# STM32F446xx_Schematic_design.net
KiCad netlist of a schematic drawn in Altium Designer
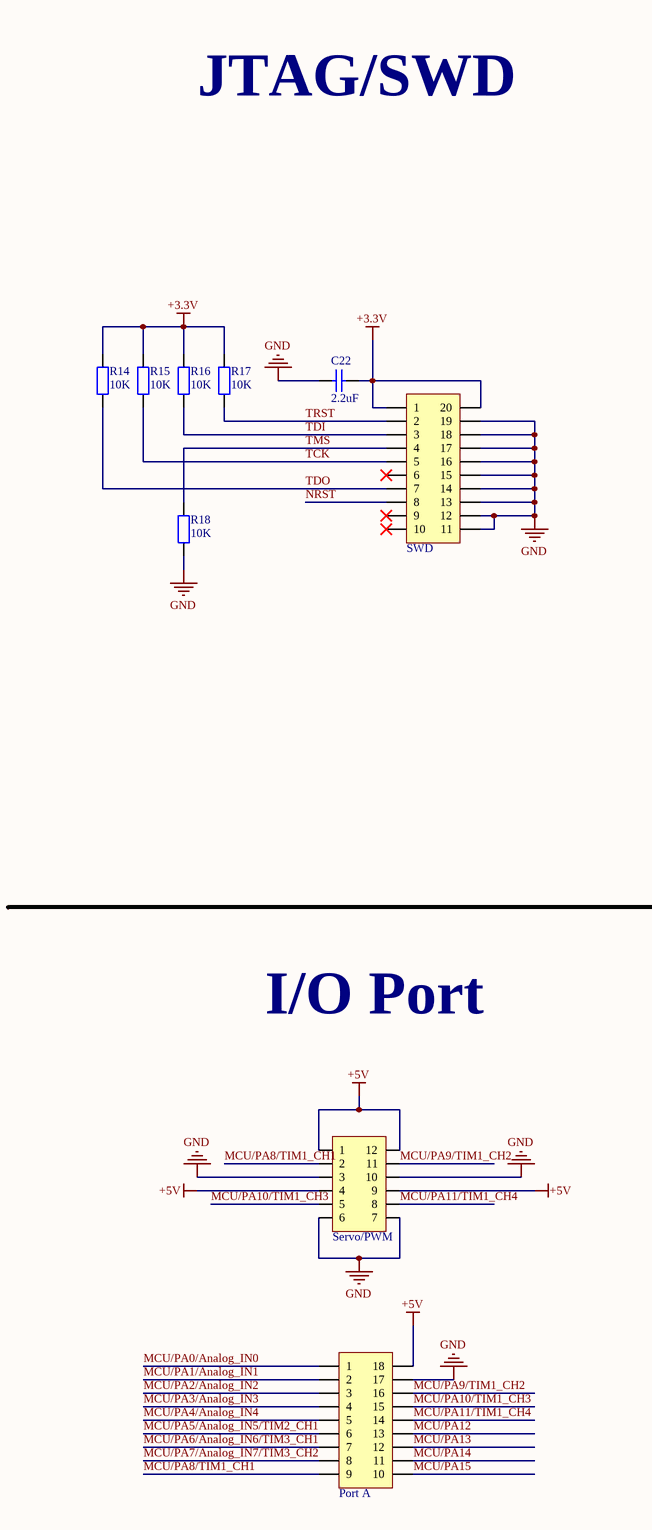
[diagram p0: STM32F446xx Schematic design.SchDoc, top left]
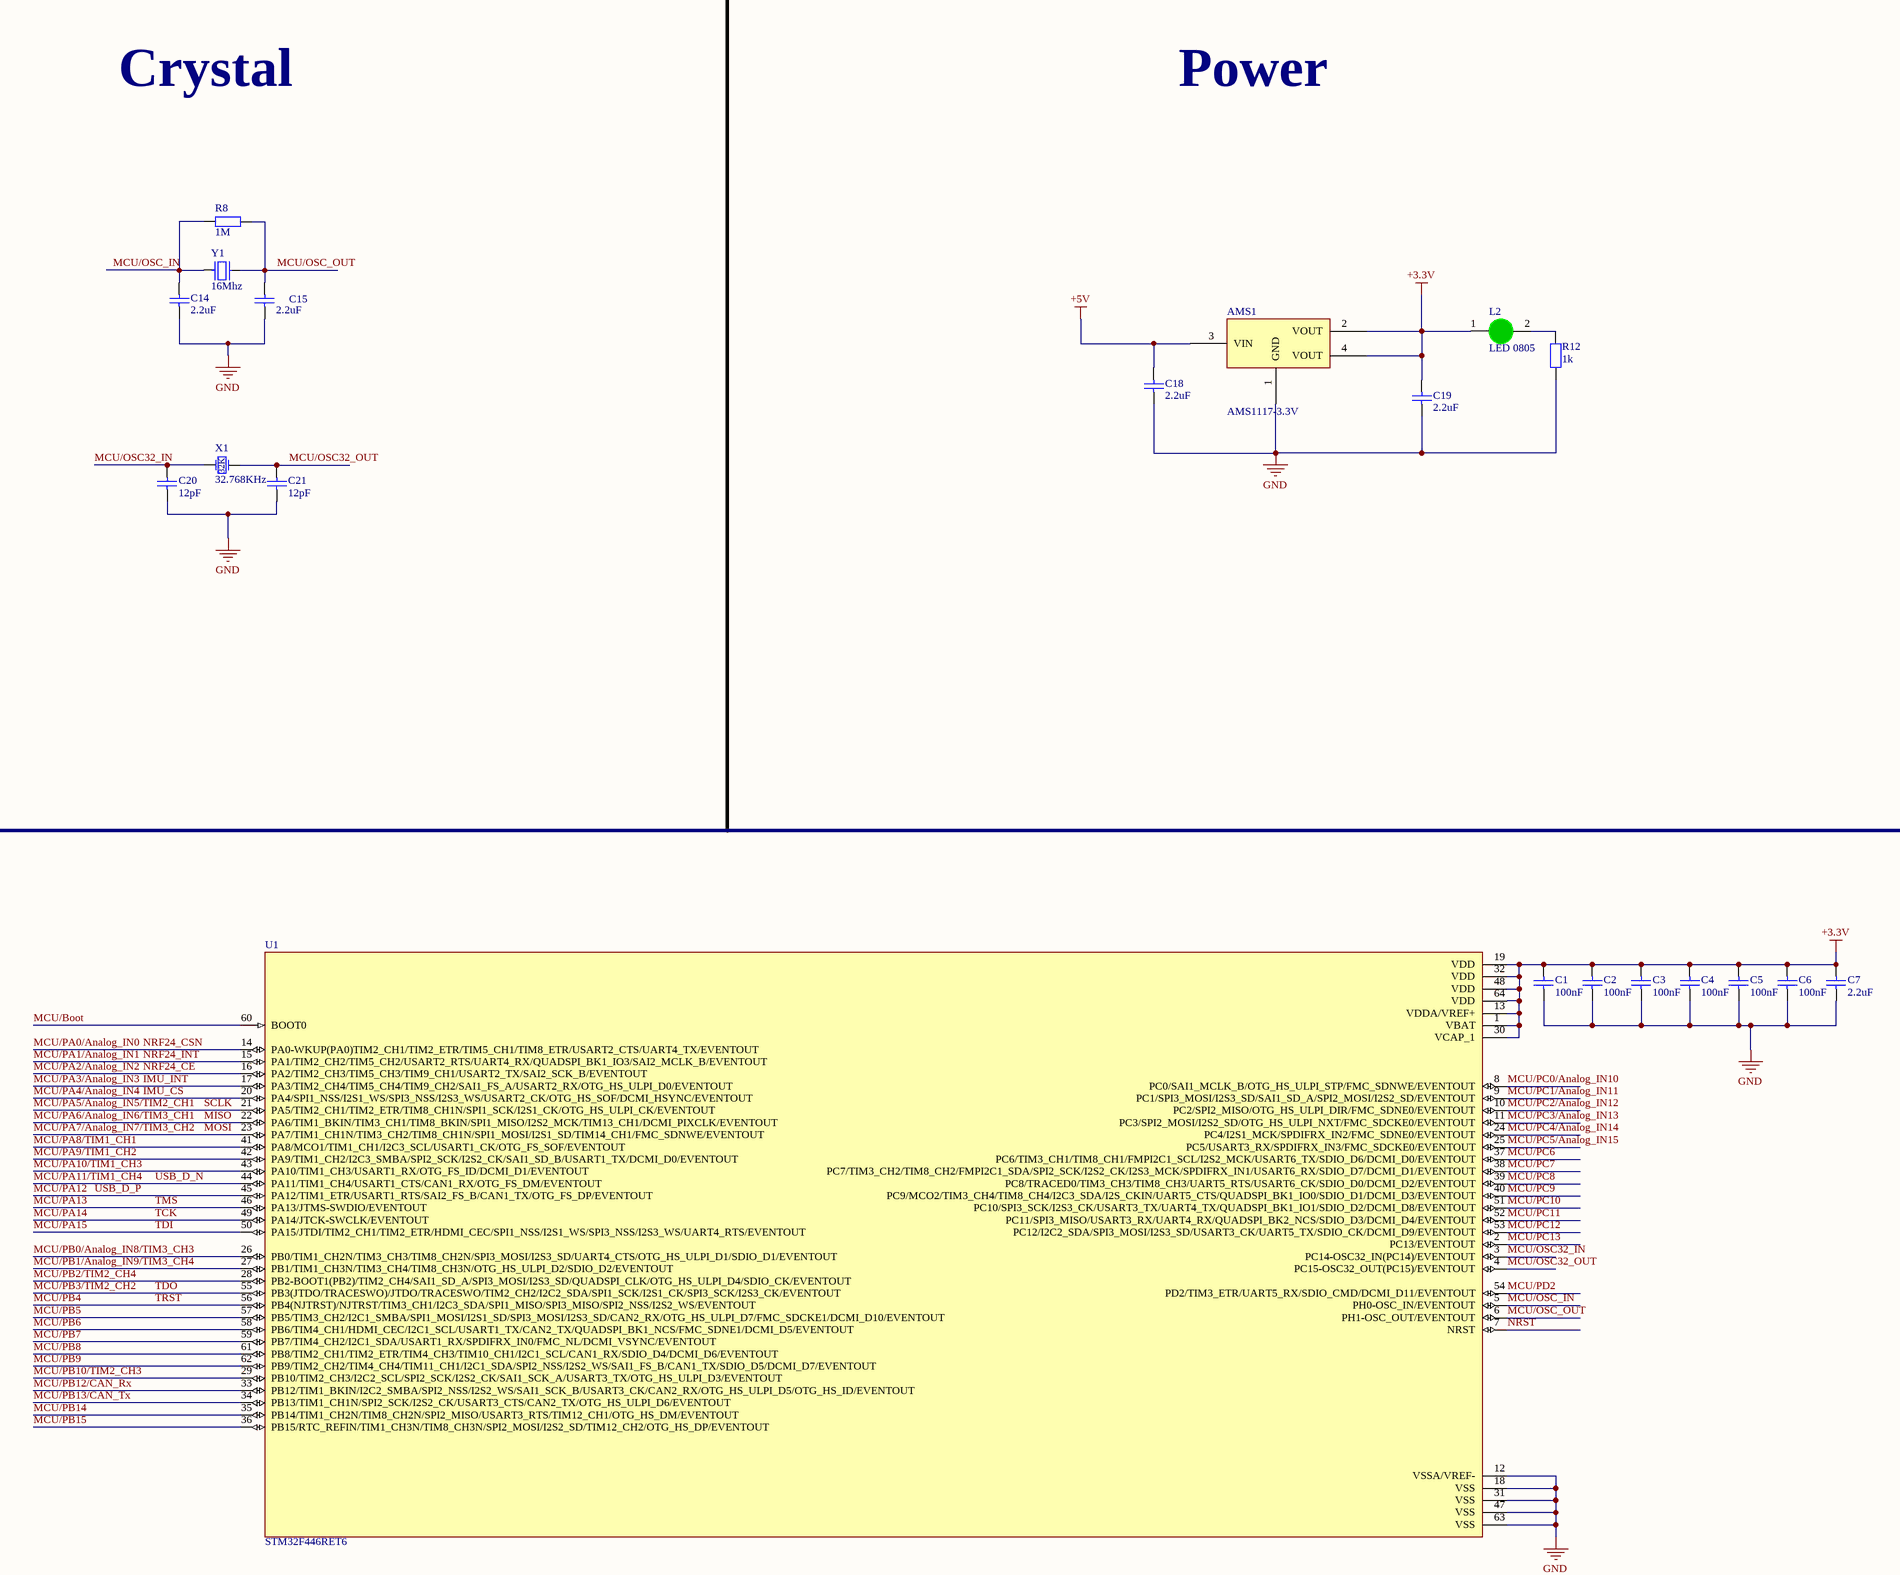
[diagram p1: STM32F446xx Schematic design.SchDoc, top middle]
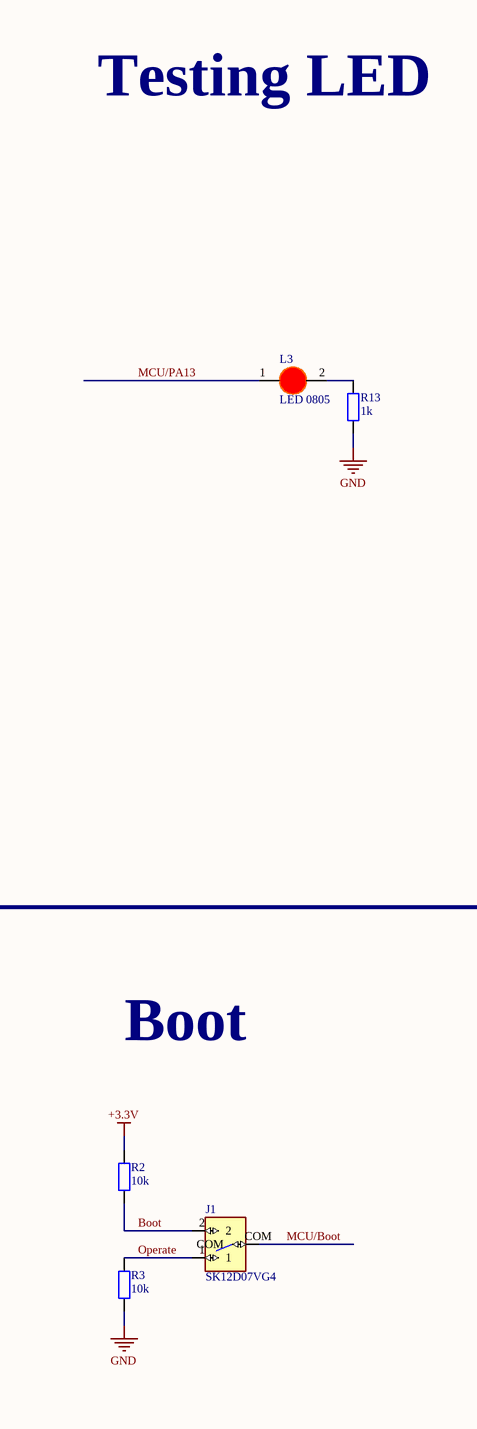
[diagram p2: STM32F446xx Schematic design.SchDoc, top right]
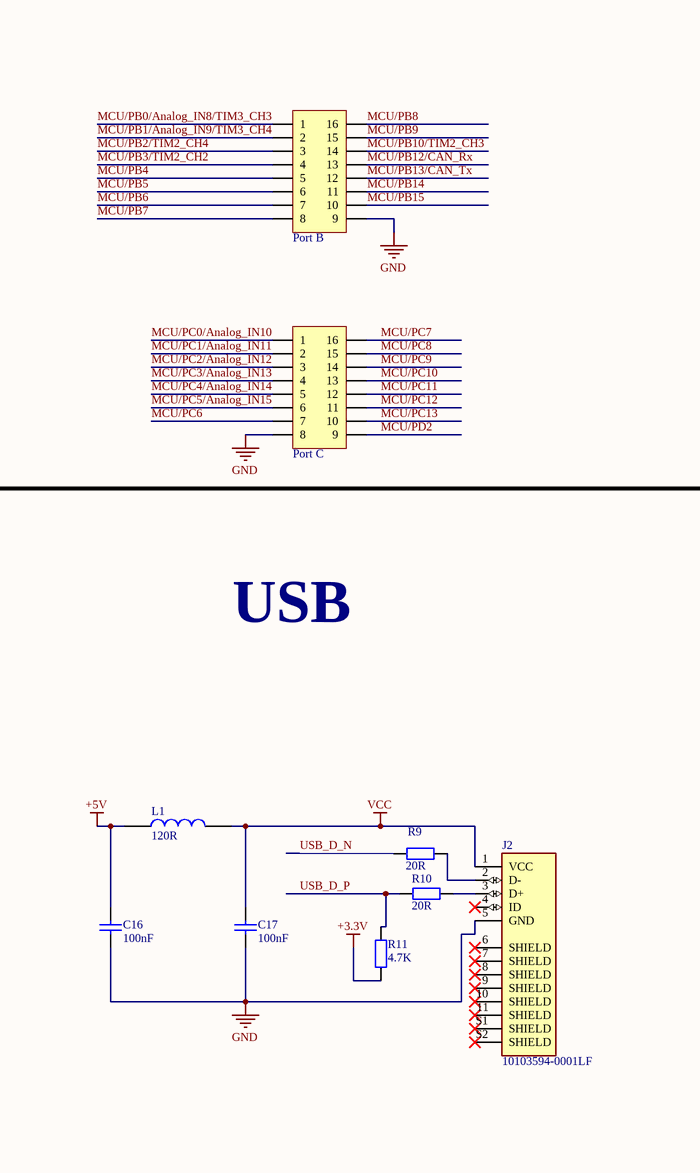
[diagram p3: STM32F446xx Schematic design.SchDoc, bottom left]
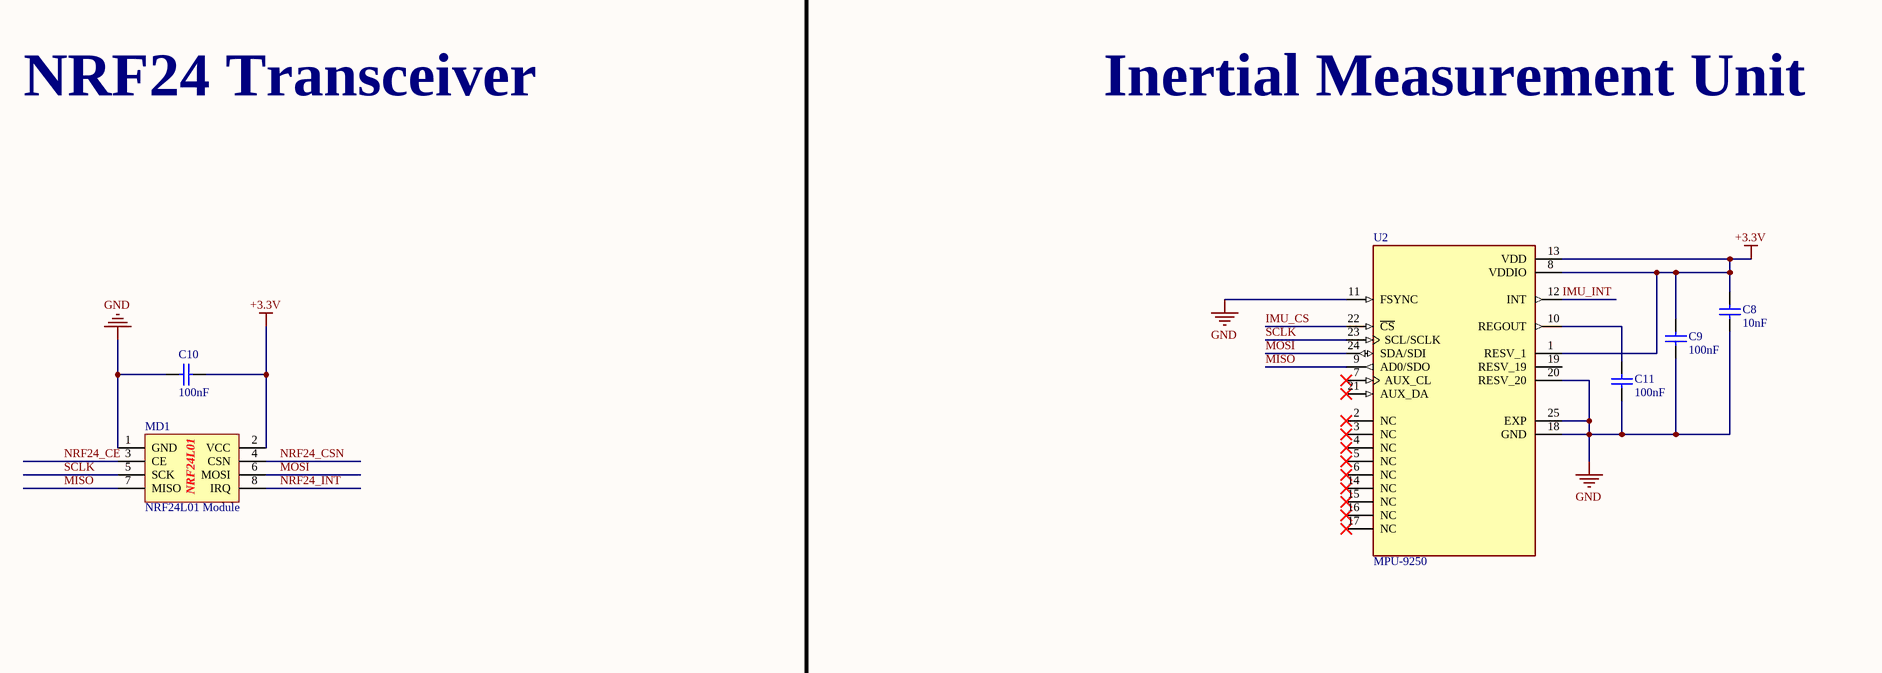
[diagram p4: STM32F446xx Schematic design.SchDoc, bottom middle]
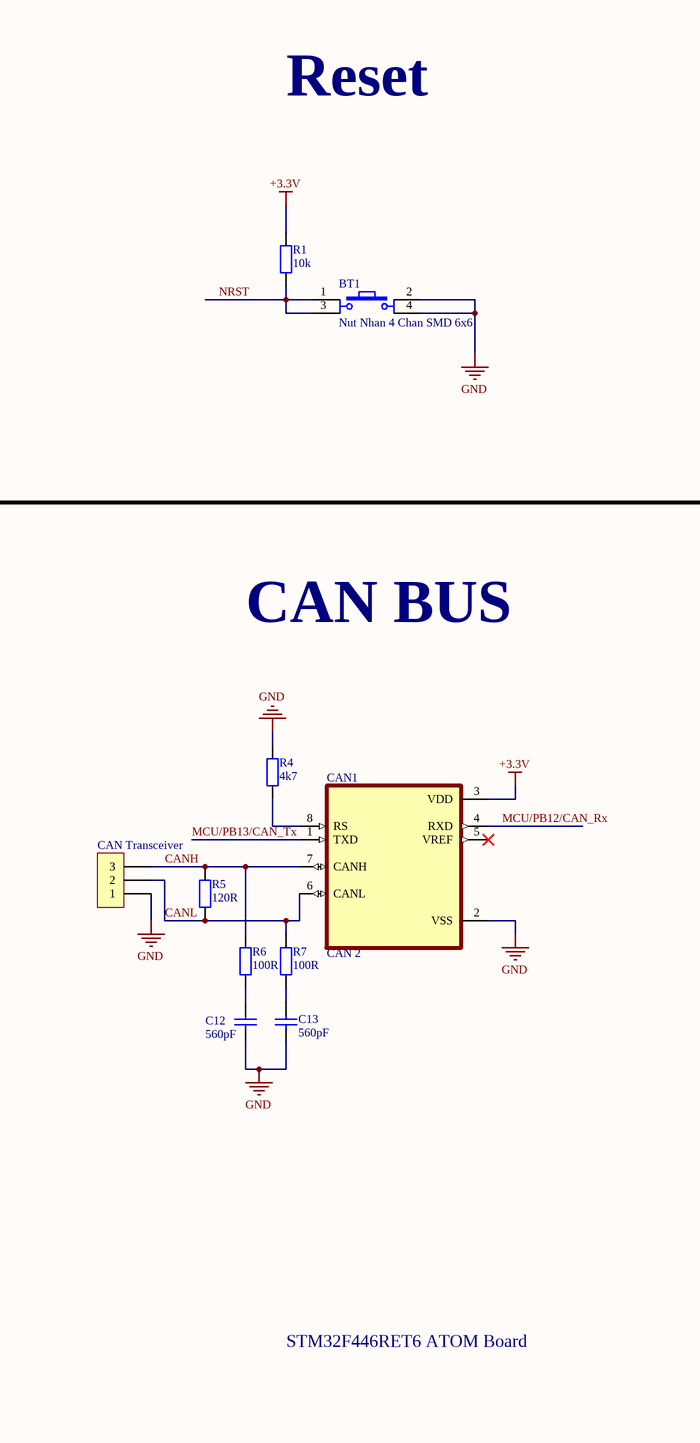
[diagram p5: STM32F446xx Schematic design.SchDoc, bottom right]

(export (version "E")
  (design (tool "Eeschema 10.0.6"))
  (components
    (comp (ref "AMS1")
      (value "AMS1117-3.3V")
      (footprint "SOT223")
      (description "Dán")
      (libsource (lib "Altium_Lib_by_KhueNguyenCreator") (part "AMS1117 SMD"))
    )
    (comp (ref "BT1")
      (value "Nut Nhan 4 Chan SMD 6x6")
      (footprint "Nut Nhan 4 Chan SMD 6x6")
      (description "Nut Nhan 4 Chan 6.2x6.2x3.5")
      (libsource (lib "Altium_Lib_by_KhueNguyenCreator") (part "Nut Nhan 4 Chan SMD 6x6"))
    )
    (comp (ref "C1")
      (value "100nF")
      (footprint "tu 0805")
      (description "Dán")
      (libsource (lib "Altium_Lib_by_KhueNguyenCreator") (part "Tu 0805 10pF 50V 10%"))
    )
    (comp (ref "C2")
      (value "100nF")
      (footprint "tu 0805")
      (description "Dán")
      (libsource (lib "Altium_Lib_by_KhueNguyenCreator") (part "Tu 0805 10pF 50V 10%"))
    )
    (comp (ref "C3")
      (value "100nF")
      (footprint "tu 0805")
      (description "Dán")
      (libsource (lib "Altium_Lib_by_KhueNguyenCreator") (part "Tu 0805 10pF 50V 10%"))
    )
    (comp (ref "C4")
      (value "100nF")
      (footprint "tu 0805")
      (description "Dán")
      (libsource (lib "Altium_Lib_by_KhueNguyenCreator") (part "Tu 0805 10pF 50V 10%"))
    )
    (comp (ref "C5")
      (value "100nF")
      (footprint "tu 0805")
      (description "Dán")
      (libsource (lib "Altium_Lib_by_KhueNguyenCreator") (part "Tu 0805 10pF 50V 10%"))
    )
    (comp (ref "C6")
      (value "100nF")
      (footprint "tu 0805")
      (description "Dán")
      (libsource (lib "Altium_Lib_by_KhueNguyenCreator") (part "Tu 0805 10pF 50V 10%"))
    )
    (comp (ref "C7")
      (value "2.2uF")
      (footprint "tu 0805")
      (description "Dán")
      (libsource (lib "Altium_Lib_by_KhueNguyenCreator") (part "Tu 0805 10pF 50V 10%"))
    )
    (comp (ref "C8")
      (value "10nF")
      (footprint "tu 0805")
      (description "Dán")
      (libsource (lib "Altium_Lib_by_KhueNguyenCreator") (part "Tu 0805 106 16V 10%"))
    )
    (comp (ref "C9")
      (value "100nF")
      (footprint "tu 0805")
      (description "Dán")
      (libsource (lib "Altium_Lib_by_KhueNguyenCreator") (part "Tu 0805 106 16V 10%"))
    )
    (comp (ref "C10")
      (value "100nF")
      (footprint "tu 0805")
      (description "Dán")
      (libsource (lib "Altium_Lib_by_KhueNguyenCreator") (part "Tu 0805 106 16V 10%"))
    )
    (comp (ref "C11")
      (value "100nF")
      (footprint "tu 0805")
      (description "Dán")
      (libsource (lib "Altium_Lib_by_KhueNguyenCreator") (part "Tu 0805 106 16V 10%"))
    )
    (comp (ref "C12")
      (value "560pF")
      (footprint "tu 0805")
      (description "Dán")
      (libsource (lib "Altium_Lib_by_KhueNguyenCreator") (part "Tu 0805 106 16V 10%"))
    )
    (comp (ref "C13")
      (value "560pF")
      (footprint "tu 0805")
      (description "Dán")
      (libsource (lib "Altium_Lib_by_KhueNguyenCreator") (part "Tu 0805 106 16V 10%"))
    )
    (comp (ref "C14")
      (value "2.2uF")
      (footprint "tu 0805")
      (description "Dán")
      (libsource (lib "Altium_Lib_by_KhueNguyenCreator") (part "Tu 0805 10pF 50V 10%"))
    )
    (comp (ref "C15")
      (value "2.2uF")
      (footprint "tu 0805")
      (description "Dán")
      (libsource (lib "Altium_Lib_by_KhueNguyenCreator") (part "Tu 0805 10pF 50V 10%"))
    )
    (comp (ref "C16")
      (value "100nF")
      (footprint "tu 0805")
      (description "Dán")
      (libsource (lib "Altium_Lib_by_KhueNguyenCreator") (part "Tu 0805 106 16V 10%"))
    )
    (comp (ref "C17")
      (value "100nF")
      (footprint "tu 0805")
      (description "Dán")
      (libsource (lib "Altium_Lib_by_KhueNguyenCreator") (part "Tu 0805 106 16V 10%"))
    )
    (comp (ref "C18")
      (value "2.2uF")
      (footprint "tu 0805")
      (description "Dán")
      (libsource (lib "Altium_Lib_by_KhueNguyenCreator") (part "Tu 0805 10pF 50V 10%"))
    )
    (comp (ref "C19")
      (value "2.2uF")
      (footprint "tu 0805")
      (description "Dán")
      (libsource (lib "Altium_Lib_by_KhueNguyenCreator") (part "Tu 0805 10pF 50V 10%"))
    )
    (comp (ref "C20")
      (value "12pF")
      (footprint "tu 0805")
      (description "Dán")
      (libsource (lib "Altium_Lib_by_KhueNguyenCreator") (part "Tu 0805 10pF 50V 10%"))
    )
    (comp (ref "C21")
      (value "12pF")
      (footprint "tu 0805")
      (description "Dán")
      (libsource (lib "Altium_Lib_by_KhueNguyenCreator") (part "Tu 0805 10pF 50V 10%"))
    )
    (comp (ref "C22")
      (value "2.2uF")
      (footprint "tu 0805")
      (description "Dán")
      (libsource (lib "Altium_Lib_by_KhueNguyenCreator") (part "Tu 0805 10pF 50V 10%"))
    )
    (comp (ref "CAN 1")
      (value "CAN Transceiver")
      (footprint "XH2.54M-3")
      (description "Cắm")
      (libsource (lib "Altium_Lib_by_KhueNguyenCreator") (part "Header 3P 2.54 Duc Thang"))
    )
    (comp (ref "CAN1")
      (value "CAN 2")
      (footprint "MCP2551-I_SN:SOIC127P599X175-8N")
      (fields
        (field (name "MF") "{'manufacturer': u'Microchip Technology'}")
        (field (name "MP") "MCP2551-I/SN")
      )
      (libsource (lib "*") (part "MCP2551-I/SN"))
    )
    (comp (ref "J1")
      (value "SK12D07VG4")
      (footprint "SK12D07VG4")
      (description "Switch Slide ON ON SPDT Side Slide 0.3A 30VDC PC Pins Bracket Mount/Through Hole Bulk")
      (fields (field (name "MF") "C&K"))
      (libsource (lib "SK12D07VG4") (part "SK12D07VG4"))
    )
    (comp (ref "J2")
      (value "10103594-0001LF")
      (footprint "10103594-0001LF:AMPHENOL_10103594-0001LF")
      (description "USB - micro B USB 2.0 Receptacle Connector 5 Position Surface Mount, Right Angle; Through Hole")
      (fields (field (name "MF") "{'manufacturer': u'FCI Connectors'}"))
      (libsource (lib "*") (part "10103594-0001LF"))
    )
    (comp (ref "L1")
      (value "120R")
      (footprint "IND-0603 (1608)")
      (description "IND-FERRITE BEAD 23 OHM  4A 0603 1LN")
      (fields (field (name "MPN") "FBMJ1608HM230NT"))
      (libsource (lib "BYTECH_HW_LIB_2019 (1)") (part "FBMJ1608HM230NT"))
    )
    (comp (ref "L2")
      (value "LED 0805")
      (footprint "LED-0805-Green")
      (description "Dán")
      (libsource (lib "Altium_Lib_by_KhueNguyenCreator") (part "LED 0805 Xanh La"))
    )
    (comp (ref "L3")
      (value "LED 0805")
      (footprint "LED-0805-Red")
      (description "Dán")
      (libsource (lib "Altium_Lib_by_KhueNguyenCreator") (part "LED 0805 Do"))
    )
    (comp (ref "MD1")
      (value "NRF24L01 Module")
      (footprint "NRF24L01")
      (libsource (lib "Altium_Lib_by_KhueNguyenCreator") (part "NRF24L01 Module"))
    )
    (comp (ref "Port A1")
      (value "Port A")
      (footprint "JP 2x9 DT")
      (description "Cắm")
      (libsource (lib "Altium_Lib_by_KhueNguyenCreator") (part "JP 2x9 2.54 Duc Thang"))
    )
    (comp (ref "Port B1")
      (value "Port B")
      (footprint "JP 2x8 DT")
      (description "Cắm")
      (libsource (lib "Altium_Lib_by_KhueNguyenCreator") (part "JP 2x8 2.54 Duc Thang"))
    )
    (comp (ref "Port C1")
      (value "Port C")
      (footprint "JP 2x8 DT")
      (description "Cắm")
      (libsource (lib "Altium_Lib_by_KhueNguyenCreator") (part "JP 2x8 2.54 Duc Thang"))
    )
    (comp (ref "R1")
      (value "10k")
      (footprint "tro smd 0805")
      (description "Dán")
      (libsource (lib "Altium_Lib_by_KhueNguyenCreator") (part "Tro 0805 1% 1k"))
    )
    (comp (ref "R2")
      (value "10k")
      (footprint "tro smd 0805")
      (description "Dán")
      (libsource (lib "Altium_Lib_by_KhueNguyenCreator") (part "Tro 0805 1% 1k"))
    )
    (comp (ref "R3")
      (value "10k")
      (footprint "tro smd 0805")
      (description "Dán")
      (libsource (lib "Altium_Lib_by_KhueNguyenCreator") (part "Tro 0805 1% 1k"))
    )
    (comp (ref "R4")
      (value "4k7")
      (footprint "tro smd 0805")
      (description "Dán")
      (libsource (lib "Altium_Lib_by_KhueNguyenCreator") (part "Tro 0805 1% 10k"))
    )
    (comp (ref "R5")
      (value "120R")
      (footprint "tro smd 0805")
      (description "Dán")
      (libsource (lib "Altium_Lib_by_KhueNguyenCreator") (part "Tro 0805 1% 10k"))
    )
    (comp (ref "R6")
      (value "100R")
      (footprint "tro smd 0805")
      (description "Dán")
      (libsource (lib "Altium_Lib_by_KhueNguyenCreator") (part "Tro 0805 1% 10k"))
    )
    (comp (ref "R7")
      (value "100R")
      (footprint "tro smd 0805")
      (description "Dán")
      (libsource (lib "Altium_Lib_by_KhueNguyenCreator") (part "Tro 0805 1% 10k"))
    )
    (comp (ref "R8")
      (value "1M")
      (footprint "tro smd 0805")
      (description "Dán")
      (libsource (lib "Altium_Lib_by_KhueNguyenCreator") (part "Tro 0805 1% 1k"))
    )
    (comp (ref "R9")
      (value "20R")
      (footprint "tro smd 0805")
      (description "Dán")
      (libsource (lib "Altium_Lib_by_KhueNguyenCreator") (part "Tro 0805 1% 10k"))
    )
    (comp (ref "R10")
      (value "20R")
      (footprint "tro smd 0805")
      (description "Dán")
      (libsource (lib "Altium_Lib_by_KhueNguyenCreator") (part "Tro 0805 1% 10k"))
    )
    (comp (ref "R11")
      (value "4.7K")
      (footprint "tro smd 0805")
      (description "Dán")
      (libsource (lib "Altium_Lib_by_KhueNguyenCreator") (part "Tro 0805 1% 10k"))
    )
    (comp (ref "R12")
      (value "1k")
      (footprint "tro smd 0805")
      (description "Dán")
      (libsource (lib "Altium_Lib_by_KhueNguyenCreator") (part "Tro 0805 1% 1k"))
    )
    (comp (ref "R13")
      (value "1k")
      (footprint "tro smd 0805")
      (description "Dán")
      (libsource (lib "Altium_Lib_by_KhueNguyenCreator") (part "Tro 0805 1% 1k"))
    )
    (comp (ref "R14")
      (value "10K")
      (footprint "tro smd 0805")
      (description "Dán")
      (libsource (lib "Altium_Lib_by_KhueNguyenCreator") (part "Tro 0805 1% 10k"))
    )
    (comp (ref "R15")
      (value "10K")
      (footprint "tro smd 0805")
      (description "Dán")
      (libsource (lib "Altium_Lib_by_KhueNguyenCreator") (part "Tro 0805 1% 10k"))
    )
    (comp (ref "R16")
      (value "10K")
      (footprint "tro smd 0805")
      (description "Dán")
      (libsource (lib "Altium_Lib_by_KhueNguyenCreator") (part "Tro 0805 1% 10k"))
    )
    (comp (ref "R17")
      (value "10K")
      (footprint "tro smd 0805")
      (description "Dán")
      (libsource (lib "Altium_Lib_by_KhueNguyenCreator") (part "Tro 0805 1% 10k"))
    )
    (comp (ref "R18")
      (value "10K")
      (footprint "tro smd 0805")
      (description "Dán")
      (libsource (lib "Altium_Lib_by_KhueNguyenCreator") (part "Tro 0805 1% 10k"))
    )
    (comp (ref "Servo/PWM1")
      (value "Servo/PWM")
      (footprint "JP 2x6 DT")
      (description "Cắm")
      (libsource (lib "Altium_Lib_by_KhueNguyenCreator") (part "JP 2x6 2.54 Duc Thang"))
    )
    (comp (ref "SWD")
      (value "SWD")
      (footprint "JP 2x10 DT")
      (description "Cắm")
      (libsource (lib "Altium_Lib_by_KhueNguyenCreator") (part "JP 2x10 2.54 Duc Thang"))
    )
    (comp (ref "U1")
      (value "STM32F446RET6")
      (footprint "QFP50P1200X1200X160-64N")
      (description "MCU 32-Bit STM32 ARM Cortex M4 RISC 512KB Flash 2.5V/3.3V 64-Pin LQFP Tray")
      (fields (field (name "MF") "{'manufacturer': u'STMicroelectronics'}"))
      (libsource (lib "SnapEDA_Library") (part "STM32F446RET6"))
    )
    (comp (ref "U2")
      (value "MPU-9250")
      (footprint "MPU-9250:QFN40P300X300X105-25N")
      (fields (field (name "MF") "{'manufacturer': u'TDK InvenSense'}"))
      (libsource (lib "*") (part "MPU-9250"))
    )
    (comp (ref "X1")
      (value "32.768KHz")
      (footprint "Crystal_ABS07_SMD-3.2x1.5MM")
      (description "CRYSTAL 32.7680KHZ 12.5pF SMD")
      (fields (field (name "MPN") "ABS07-32.768KHZ-T"))
      (libsource (lib "BYTECH_HW_LIB_2019 (1)") (part "ABS07-32.768KHZ-T"))
    )
    (comp (ref "Y1")
      (value "16Mhz")
      (footprint "Thach Anh 2 chan cam")
      (description "Crystal For all Crystal 2pin.")
      (libsource (lib "Altium_Lib_by_KhueNguyenCreator") (part "Thach Anh 2 chan Cam"))
    )
  )
  (nets
    (net (code "1") (name "+3.3V") (class "Default")
      (node (ref "AMS1") (pin "2") (pinfunction "VOUT_2") (pintype "passive"))
      (node (ref "AMS1") (pin "4") (pinfunction "VOUT_4") (pintype "passive"))
      (node (ref "C1") (pin "1") (pinfunction "1_1") (pintype "passive"))
      (node (ref "C10") (pin "1") (pinfunction "1_1") (pintype "passive"))
      (node (ref "C19") (pin "1") (pinfunction "1_1") (pintype "passive"))
      (node (ref "C2") (pin "1") (pinfunction "1_1") (pintype "passive"))
      (node (ref "C22") (pin "2") (pinfunction "2_2") (pintype "passive"))
      (node (ref "C3") (pin "1") (pinfunction "1_1") (pintype "passive"))
      (node (ref "C4") (pin "1") (pinfunction "1_1") (pintype "passive"))
      (node (ref "C5") (pin "1") (pinfunction "1_1") (pintype "passive"))
      (node (ref "C6") (pin "1") (pinfunction "1_1") (pintype "passive"))
      (node (ref "C7") (pin "1") (pinfunction "1_1") (pintype "passive"))
      (node (ref "C8") (pin "1") (pinfunction "1_1") (pintype "passive"))
      (node (ref "C9") (pin "1") (pinfunction "1_1") (pintype "passive"))
      (node (ref "CAN1") (pin "3") (pinfunction "VDD_3") (pintype "power_in"))
      (node (ref "L2") (pin "1") (pinfunction "A_1") (pintype "passive"))
      (node (ref "MD1") (pin "2") (pinfunction "VCC_2") (pintype "passive"))
      (node (ref "R1") (pin "1") (pinfunction "1_1") (pintype "passive"))
      (node (ref "R11") (pin "2") (pinfunction "2_2") (pintype "passive"))
      (node (ref "R14") (pin "2") (pinfunction "2_2") (pintype "passive"))
      (node (ref "R15") (pin "2") (pinfunction "2_2") (pintype "passive"))
      (node (ref "R16") (pin "2") (pinfunction "2_2") (pintype "passive"))
      (node (ref "R17") (pin "2") (pinfunction "2_2") (pintype "passive"))
      (node (ref "R2") (pin "1") (pinfunction "1_1") (pintype "passive"))
      (node (ref "SWD") (pin "1") (pinfunction "1_1") (pintype "passive"))
      (node (ref "SWD") (pin "20") (pinfunction "20_20") (pintype "passive"))
      (node (ref "U1") (pin "1") (pinfunction "VBAT_1") (pintype "power_in"))
      (node (ref "U1") (pin "13") (pinfunction "VDDA/VREF+_13") (pintype "power_in"))
      (node (ref "U1") (pin "19") (pinfunction "VDD_19") (pintype "power_in"))
      (node (ref "U1") (pin "30") (pinfunction "VCAP_1_30") (pintype "power_in"))
      (node (ref "U1") (pin "32") (pinfunction "VDD_32") (pintype "power_in"))
      (node (ref "U1") (pin "48") (pinfunction "VDD_48") (pintype "power_in"))
      (node (ref "U1") (pin "64") (pinfunction "VDD_64") (pintype "power_in"))
      (node (ref "U2") (pin "1") (pinfunction "RESV_1_1") (pintype "power_in"))
      (node (ref "U2") (pin "13") (pinfunction "VDD_13") (pintype "power_in"))
      (node (ref "U2") (pin "8") (pinfunction "VDDIO_8") (pintype "power_in"))
    )
    (net (code "2") (name "+5V") (class "Default")
      (node (ref "AMS1") (pin "3") (pinfunction "VIN_3") (pintype "passive"))
      (node (ref "C16") (pin "1") (pinfunction "1_1") (pintype "passive"))
      (node (ref "C18") (pin "1") (pinfunction "1_1") (pintype "passive"))
      (node (ref "L1") (pin "1") (pinfunction "1_1") (pintype "passive"))
      (node (ref "Port A1") (pin "18") (pinfunction "18_18") (pintype "passive"))
      (node (ref "Servo/PWM1") (pin "1") (pinfunction "1_1") (pintype "passive"))
      (node (ref "Servo/PWM1") (pin "12") (pinfunction "12_12") (pintype "passive"))
      (node (ref "Servo/PWM1") (pin "4") (pinfunction "4_4") (pintype "passive"))
      (node (ref "Servo/PWM1") (pin "9") (pinfunction "9_9") (pintype "passive"))
    )
    (net (code "3") (name "/Boot") (class "Default")
      (node (ref "J1") (pin "2") (pinfunction "2_2") (pintype "bidirectional"))
      (node (ref "R2") (pin "2") (pinfunction "2_2") (pintype "passive"))
    )
    (net (code "4") (name "/CANH") (class "Default")
      (node (ref "CAN 1") (pin "3") (pinfunction "3_3") (pintype "passive"))
      (node (ref "CAN1") (pin "7") (pinfunction "CANH_7") (pintype "bidirectional"))
      (node (ref "R5") (pin "2") (pinfunction "2_2") (pintype "passive"))
      (node (ref "R6") (pin "2") (pinfunction "2_2") (pintype "passive"))
    )
    (net (code "5") (name "/CANL") (class "Default")
      (node (ref "CAN 1") (pin "2") (pinfunction "2_2") (pintype "passive"))
      (node (ref "CAN1") (pin "6") (pinfunction "CANL_6") (pintype "bidirectional"))
      (node (ref "R5") (pin "1") (pinfunction "1_1") (pintype "passive"))
      (node (ref "R7") (pin "2") (pinfunction "2_2") (pintype "passive"))
    )
    (net (code "6") (name "/IMU_CS") (class "Default")
      (node (ref "Port A1") (pin "5") (pinfunction "5_5") (pintype "passive"))
      (node (ref "U1") (pin "20") (pinfunction "PA4/SPI1_NSS/I2S1_WS/SPI3_NSS/I2S3_WS/USART2_CK/OTG_HS_SOF/DCMI_HSYNC/EVENTOUT_20") (pintype "bidirectional"))
      (node (ref "U2") (pin "22") (pinfunction "~{CS}_22") (pintype "input"))
    )
    (net (code "7") (name "/IMU_INT") (class "Default")
      (node (ref "Port A1") (pin "4") (pinfunction "4_4") (pintype "passive"))
      (node (ref "U1") (pin "17") (pinfunction "PA3/TIM2_CH4/TIM5_CH4/TIM9_CH2/SAI1_FS_A/USART2_RX/OTG_HS_ULPI_D0/EVENTOUT_17") (pintype "bidirectional"))
      (node (ref "U2") (pin "12") (pinfunction "INT_12") (pintype "output"))
    )
    (net (code "8") (name "/MCU{slash}Boot") (class "Default")
      (node (ref "J1") (pin "COM") (pinfunction "COM_COM") (pintype "bidirectional"))
      (node (ref "U1") (pin "60") (pinfunction "BOOT0_60") (pintype "input"))
    )
    (net (code "9") (name "/MCU{slash}OSC32_IN") (class "Default")
      (node (ref "C20") (pin "1") (pinfunction "1_1") (pintype "passive"))
      (node (ref "U1") (pin "3") (pinfunction "PC14-OSC32_IN(PC14)/EVENTOUT_3") (pintype "bidirectional"))
      (node (ref "X1") (pin "1") (pinfunction "OSC1_1") (pintype "passive"))
    )
    (net (code "10") (name "/MCU{slash}OSC32_OUT") (class "Default")
      (node (ref "C21") (pin "1") (pinfunction "1_1") (pintype "passive"))
      (node (ref "U1") (pin "4") (pinfunction "PC15-OSC32_OUT(PC15)/EVENTOUT_4") (pintype "bidirectional"))
      (node (ref "X1") (pin "2") (pinfunction "OSC2_2") (pintype "passive"))
    )
    (net (code "11") (name "/MCU{slash}OSC_IN") (class "Default")
      (node (ref "C14") (pin "1") (pinfunction "1_1") (pintype "passive"))
      (node (ref "R8") (pin "1") (pinfunction "1_1") (pintype "passive"))
      (node (ref "U1") (pin "5") (pinfunction "PH0-OSC_IN/EVENTOUT_5") (pintype "bidirectional"))
      (node (ref "Y1") (pin "1") (pinfunction "1_1") (pintype "passive"))
    )
    (net (code "12") (name "/MCU{slash}OSC_OUT") (class "Default")
      (node (ref "C15") (pin "1") (pinfunction "1_1") (pintype "passive"))
      (node (ref "R8") (pin "2") (pinfunction "2_2") (pintype "passive"))
      (node (ref "U1") (pin "6") (pinfunction "PH1-OSC_OUT/EVENTOUT_6") (pintype "bidirectional"))
      (node (ref "Y1") (pin "2") (pinfunction "2_2") (pintype "passive"))
    )
    (net (code "13") (name "/MCU{slash}PA0{slash}Analog_IN0") (class "Default")
      (node (ref "MD1") (pin "4") (pinfunction "CSN_4") (pintype "passive"))
      (node (ref "Port A1") (pin "1") (pinfunction "1_1") (pintype "passive"))
      (node (ref "U1") (pin "14") (pinfunction "PA0-WKUP(PA0)TIM2_CH1/TIM2_ETR/TIM5_CH1/TIM8_ETR/USART2_CTS/UART4_TX/EVENTOUT_14") (pintype "bidirectional"))
    )
    (net (code "14") (name "/MCU{slash}PA1{slash}Analog_IN1") (class "Default")
      (node (ref "MD1") (pin "8") (pinfunction "IRQ_8") (pintype "passive"))
      (node (ref "Port A1") (pin "2") (pinfunction "2_2") (pintype "passive"))
      (node (ref "U1") (pin "15") (pinfunction "PA1/TIM2_CH2/TIM5_CH2/USART2_RTS/UART4_RX/QUADSPI_BK1_IO3/SAI2_MCLK_B/EVENTOUT_15") (pintype "bidirectional"))
    )
    (net (code "15") (name "/MCU{slash}PA2{slash}Analog_IN2") (class "Default")
      (node (ref "MD1") (pin "3") (pinfunction "CE_3") (pintype "passive"))
      (node (ref "Port A1") (pin "3") (pinfunction "3_3") (pintype "passive"))
      (node (ref "U1") (pin "16") (pinfunction "PA2/TIM2_CH3/TIM5_CH3/TIM9_CH1/USART2_TX/SAI2_SCK_B/EVENTOUT_16") (pintype "bidirectional"))
    )
    (net (code "16") (name "/MCU{slash}PA5{slash}Analog_IN5{slash}TIM2_CH1") (class "Default")
      (node (ref "MD1") (pin "5") (pinfunction "SCK_5") (pintype "passive"))
      (node (ref "Port A1") (pin "6") (pinfunction "6_6") (pintype "passive"))
      (node (ref "U1") (pin "21") (pinfunction "PA5/TIM2_CH1/TIM2_ETR/TIM8_CH1N/SPI1_SCK/I2S1_CK/OTG_HS_ULPI_CK/EVENTOUT_21") (pintype "bidirectional"))
      (node (ref "U2") (pin "23") (pinfunction "SCL/SCLK_23") (pintype "input"))
    )
    (net (code "17") (name "/MCU{slash}PA6{slash}Analog_IN6{slash}TIM3_CH1") (class "Default")
      (node (ref "MD1") (pin "7") (pinfunction "MISO_7") (pintype "passive"))
      (node (ref "Port A1") (pin "7") (pinfunction "7_7") (pintype "passive"))
      (node (ref "U1") (pin "22") (pinfunction "PA6/TIM1_BKIN/TIM3_CH1/TIM8_BKIN/SPI1_MISO/I2S2_MCK/TIM13_CH1/DCMI_PIXCLK/EVENTOUT_22") (pintype "bidirectional"))
      (node (ref "U2") (pin "9") (pinfunction "AD0/SDO_9") (pintype "output"))
    )
    (net (code "18") (name "/MCU{slash}PA7{slash}Analog_IN7{slash}TIM3_CH2") (class "Default")
      (node (ref "MD1") (pin "6") (pinfunction "MOSI_6") (pintype "passive"))
      (node (ref "Port A1") (pin "8") (pinfunction "8_8") (pintype "passive"))
      (node (ref "U1") (pin "23") (pinfunction "PA7/TIM1_CH1N/TIM3_CH2/TIM8_CH1N/SPI1_MOSI/I2S1_SD/TIM14_CH1/FMC_SDNWE/EVENTOUT_23") (pintype "bidirectional"))
      (node (ref "U2") (pin "24") (pinfunction "SDA/SDI_24") (pintype "bidirectional"))
    )
    (net (code "19") (name "/MCU{slash}PA8{slash}TIM1_CH1") (class "Default")
      (node (ref "Port A1") (pin "9") (pinfunction "9_9") (pintype "passive"))
      (node (ref "Servo/PWM1") (pin "2") (pinfunction "2_2") (pintype "passive"))
      (node (ref "U1") (pin "41") (pinfunction "PA8/MCO1/TIM1_CH1/I2C3_SCL/USART1_CK/OTG_FS_SOF/EVENTOUT_41") (pintype "bidirectional"))
    )
    (net (code "20") (name "/MCU{slash}PA9{slash}TIM1_CH2") (class "Default")
      (node (ref "Port A1") (pin "16") (pinfunction "16_16") (pintype "passive"))
      (node (ref "Servo/PWM1") (pin "11") (pinfunction "11_11") (pintype "passive"))
      (node (ref "U1") (pin "42") (pinfunction "PA9/TIM1_CH2/I2C3_SMBA/SPI2_SCK/I2S2_CK/SAI1_SD_B/USART1_TX/DCMI_D0/EVENTOUT_42") (pintype "bidirectional"))
    )
    (net (code "21") (name "/MCU{slash}PA10{slash}TIM1_CH3") (class "Default")
      (node (ref "Port A1") (pin "15") (pinfunction "15_15") (pintype "passive"))
      (node (ref "Servo/PWM1") (pin "5") (pinfunction "5_5") (pintype "passive"))
      (node (ref "U1") (pin "43") (pinfunction "PA10/TIM1_CH3/USART1_RX/OTG_FS_ID/DCMI_D1/EVENTOUT_43") (pintype "bidirectional"))
    )
    (net (code "22") (name "/MCU{slash}PA11{slash}TIM1_CH4") (class "Default")
      (node (ref "Port A1") (pin "14") (pinfunction "14_14") (pintype "passive"))
      (node (ref "R9") (pin "2") (pinfunction "2_2") (pintype "passive"))
      (node (ref "Servo/PWM1") (pin "8") (pinfunction "8_8") (pintype "passive"))
      (node (ref "U1") (pin "44") (pinfunction "PA11/TIM1_CH4/USART1_CTS/CAN1_RX/OTG_FS_DM/EVENTOUT_44") (pintype "bidirectional"))
    )
    (net (code "23") (name "/MCU{slash}PA12") (class "Default")
      (node (ref "Port A1") (pin "13") (pinfunction "13_13") (pintype "passive"))
      (node (ref "R10") (pin "2") (pinfunction "2_2") (pintype "passive"))
      (node (ref "R11") (pin "1") (pinfunction "1_1") (pintype "passive"))
      (node (ref "U1") (pin "45") (pinfunction "PA12/TIM1_ETR/USART1_RTS/SAI2_FS_B/CAN1_TX/OTG_FS_DP/EVENTOUT_45") (pintype "bidirectional"))
    )
    (net (code "24") (name "/MCU{slash}PA13") (class "Default")
      (node (ref "L3") (pin "1") (pinfunction "A_1") (pintype "passive"))
      (node (ref "Port A1") (pin "12") (pinfunction "12_12") (pintype "passive"))
      (node (ref "R18") (pin "2") (pinfunction "2_2") (pintype "passive"))
      (node (ref "SWD") (pin "4") (pinfunction "4_4") (pintype "passive"))
      (node (ref "U1") (pin "46") (pinfunction "PA13/JTMS-SWDIO/EVENTOUT_46") (pintype "bidirectional"))
    )
    (net (code "25") (name "/MCU{slash}PA14") (class "Default")
      (node (ref "Port A1") (pin "11") (pinfunction "11_11") (pintype "passive"))
      (node (ref "R15") (pin "1") (pinfunction "1_1") (pintype "passive"))
      (node (ref "SWD") (pin "5") (pinfunction "5_5") (pintype "passive"))
      (node (ref "U1") (pin "49") (pinfunction "PA14/JTCK-SWCLK/EVENTOUT_49") (pintype "bidirectional"))
    )
    (net (code "26") (name "/MCU{slash}PA15") (class "Default")
      (node (ref "Port A1") (pin "10") (pinfunction "10_10") (pintype "passive"))
      (node (ref "R16") (pin "1") (pinfunction "1_1") (pintype "passive"))
      (node (ref "SWD") (pin "3") (pinfunction "3_3") (pintype "passive"))
      (node (ref "U1") (pin "50") (pinfunction "PA15/JTDI/TIM2_CH1/TIM2_ETR/HDMI_CEC/SPI1_NSS/I2S1_WS/SPI3_NSS/I2S3_WS/UART4_RTS/EVENTOUT_50") (pintype "bidirectional"))
    )
    (net (code "27") (name "/MCU{slash}PB0{slash}Analog_IN8{slash}TIM3_CH3") (class "Default")
      (node (ref "Port B1") (pin "1") (pinfunction "1_1") (pintype "passive"))
      (node (ref "U1") (pin "26") (pinfunction "PB0/TIM1_CH2N/TIM3_CH3/TIM8_CH2N/SPI3_MOSI/I2S3_SD/UART4_CTS/OTG_HS_ULPI_D1/SDIO_D1/EVENTOUT_26") (pintype "bidirectional"))
    )
    (net (code "28") (name "/MCU{slash}PB1{slash}Analog_IN9{slash}TIM3_CH4") (class "Default")
      (node (ref "Port B1") (pin "2") (pinfunction "2_2") (pintype "passive"))
      (node (ref "U1") (pin "27") (pinfunction "PB1/TIM1_CH3N/TIM3_CH4/TIM8_CH3N/OTG_HS_ULPI_D2/SDIO_D2/EVENTOUT_27") (pintype "bidirectional"))
    )
    (net (code "29") (name "/MCU{slash}PB2{slash}TIM2_CH4") (class "Default")
      (node (ref "Port B1") (pin "3") (pinfunction "3_3") (pintype "passive"))
      (node (ref "U1") (pin "28") (pinfunction "PB2-BOOT1(PB2)/TIM2_CH4/SAI1_SD_A/SPI3_MOSI/I2S3_SD/QUADSPI_CLK/OTG_HS_ULPI_D4/SDIO_CK/EVENTOUT_28") (pintype "bidirectional"))
    )
    (net (code "30") (name "/MCU{slash}PB3{slash}TIM2_CH2") (class "Default")
      (node (ref "Port B1") (pin "4") (pinfunction "4_4") (pintype "passive"))
      (node (ref "R14") (pin "1") (pinfunction "1_1") (pintype "passive"))
      (node (ref "SWD") (pin "7") (pinfunction "7_7") (pintype "passive"))
      (node (ref "U1") (pin "55") (pinfunction "PB3(JTDO/TRACESWO)/JTDO/TRACESWO/TIM2_CH2/I2C2_SDA/SPI1_SCK/I2S1_CK/SPI3_SCK/I2S3_CK/EVENTOUT_55") (pintype "bidirectional"))
    )
    (net (code "31") (name "/MCU{slash}PB4") (class "Default")
      (node (ref "Port B1") (pin "5") (pinfunction "5_5") (pintype "passive"))
      (node (ref "R17") (pin "1") (pinfunction "1_1") (pintype "passive"))
      (node (ref "SWD") (pin "2") (pinfunction "2_2") (pintype "passive"))
      (node (ref "U1") (pin "56") (pinfunction "PB4(NJTRST)/NJTRST/TIM3_CH1/I2C3_SDA/SPI1_MISO/SPI3_MISO/SPI2_NSS/I2S2_WS/EVENTOUT_56") (pintype "bidirectional"))
    )
    (net (code "32") (name "/MCU{slash}PB5") (class "Default")
      (node (ref "Port B1") (pin "6") (pinfunction "6_6") (pintype "passive"))
      (node (ref "U1") (pin "57") (pinfunction "PB5/TIM3_CH2/I2C1_SMBA/SPI1_MOSI/I2S1_SD/SPI3_MOSI/I2S3_SD/CAN2_RX/OTG_HS_ULPI_D7/FMC_SDCKE1/DCMI_D10/EVENTOUT_57") (pintype "bidirectional"))
    )
    (net (code "33") (name "/MCU{slash}PB6") (class "Default")
      (node (ref "Port B1") (pin "7") (pinfunction "7_7") (pintype "passive"))
      (node (ref "U1") (pin "58") (pinfunction "PB6/TIM4_CH1/HDMI_CEC/I2C1_SCL/USART1_TX/CAN2_TX/QUADSPI_BK1_NCS/FMC_SDNE1/DCMI_D5/EVENTOUT_58") (pintype "bidirectional"))
    )
    (net (code "34") (name "/MCU{slash}PB7") (class "Default")
      (node (ref "Port B1") (pin "8") (pinfunction "8_8") (pintype "passive"))
      (node (ref "U1") (pin "59") (pinfunction "PB7/TIM4_CH2/I2C1_SDA/USART1_RX/SPDIFRX_IN0/FMC_NL/DCMI_VSYNC/EVENTOUT_59") (pintype "bidirectional"))
    )
    (net (code "35") (name "/MCU{slash}PB8") (class "Default")
      (node (ref "Port B1") (pin "16") (pinfunction "16_16") (pintype "passive"))
      (node (ref "U1") (pin "61") (pinfunction "PB8/TIM2_CH1/TIM2_ETR/TIM4_CH3/TIM10_CH1/I2C1_SCL/CAN1_RX/SDIO_D4/DCMI_D6/EVENTOUT_61") (pintype "bidirectional"))
    )
    (net (code "36") (name "/MCU{slash}PB9") (class "Default")
      (node (ref "Port B1") (pin "15") (pinfunction "15_15") (pintype "passive"))
      (node (ref "U1") (pin "62") (pinfunction "PB9/TIM2_CH2/TIM4_CH4/TIM11_CH1/I2C1_SDA/SPI2_NSS/I2S2_WS/SAI1_FS_B/CAN1_TX/SDIO_D5/DCMI_D7/EVENTOUT_62") (pintype "bidirectional"))
    )
    (net (code "37") (name "/MCU{slash}PB10{slash}TIM2_CH3") (class "Default")
      (node (ref "Port B1") (pin "14") (pinfunction "14_14") (pintype "passive"))
      (node (ref "U1") (pin "29") (pinfunction "PB10/TIM2_CH3/I2C2_SCL/SPI2_SCK/I2S2_CK/SAI1_SCK_A/USART3_TX/OTG_HS_ULPI_D3/EVENTOUT_29") (pintype "bidirectional"))
    )
    (net (code "38") (name "/MCU{slash}PB12{slash}CAN_Rx") (class "Default")
      (node (ref "CAN1") (pin "4") (pinfunction "RXD_4") (pintype "output"))
      (node (ref "Port B1") (pin "13") (pinfunction "13_13") (pintype "passive"))
      (node (ref "U1") (pin "33") (pinfunction "PB12/TIM1_BKIN/I2C2_SMBA/SPI2_NSS/I2S2_WS/SAI1_SCK_B/USART3_CK/CAN2_RX/OTG_HS_ULPI_D5/OTG_HS_ID/EVENTOUT_33") (pintype "bidirectional"))
    )
    (net (code "39") (name "/MCU{slash}PB13{slash}CAN_Tx") (class "Default")
      (node (ref "CAN1") (pin "1") (pinfunction "TXD_1") (pintype "input"))
      (node (ref "Port B1") (pin "12") (pinfunction "12_12") (pintype "passive"))
      (node (ref "U1") (pin "34") (pinfunction "PB13/TIM1_CH1N/SPI2_SCK/I2S2_CK/USART3_CTS/CAN2_TX/OTG_HS_ULPI_D6/EVENTOUT_34") (pintype "bidirectional"))
    )
    (net (code "40") (name "/MCU{slash}PB14") (class "Default")
      (node (ref "Port B1") (pin "11") (pinfunction "11_11") (pintype "passive"))
      (node (ref "U1") (pin "35") (pinfunction "PB14/TIM1_CH2N/TIM8_CH2N/SPI2_MISO/USART3_RTS/TIM12_CH1/OTG_HS_DM/EVENTOUT_35") (pintype "bidirectional"))
    )
    (net (code "41") (name "/MCU{slash}PB15") (class "Default")
      (node (ref "Port B1") (pin "10") (pinfunction "10_10") (pintype "passive"))
      (node (ref "U1") (pin "36") (pinfunction "PB15/RTC_REFIN/TIM1_CH3N/TIM8_CH3N/SPI2_MOSI/I2S2_SD/TIM12_CH2/OTG_HS_DP/EVENTOUT_36") (pintype "bidirectional"))
    )
    (net (code "42") (name "/MCU{slash}PC0{slash}Analog_IN10") (class "Default")
      (node (ref "Port C1") (pin "1") (pinfunction "1_1") (pintype "passive"))
      (node (ref "U1") (pin "8") (pinfunction "PC0/SAI1_MCLK_B/OTG_HS_ULPI_STP/FMC_SDNWE/EVENTOUT_8") (pintype "bidirectional"))
    )
    (net (code "43") (name "/MCU{slash}PC1{slash}Analog_IN11") (class "Default")
      (node (ref "Port C1") (pin "2") (pinfunction "2_2") (pintype "passive"))
      (node (ref "U1") (pin "9") (pinfunction "PC1/SPI3_MOSI/I2S3_SD/SAI1_SD_A/SPI2_MOSI/I2S2_SD/EVENTOUT_9") (pintype "bidirectional"))
    )
    (net (code "44") (name "/MCU{slash}PC2{slash}Analog_IN12") (class "Default")
      (node (ref "Port C1") (pin "3") (pinfunction "3_3") (pintype "passive"))
      (node (ref "U1") (pin "10") (pinfunction "PC2/SPI2_MISO/OTG_HS_ULPI_DIR/FMC_SDNE0/EVENTOUT_10") (pintype "bidirectional"))
    )
    (net (code "45") (name "/MCU{slash}PC3{slash}Analog_IN13") (class "Default")
      (node (ref "Port C1") (pin "4") (pinfunction "4_4") (pintype "passive"))
      (node (ref "U1") (pin "11") (pinfunction "PC3/SPI2_MOSI/I2S2_SD/OTG_HS_ULPI_NXT/FMC_SDCKE0/EVENTOUT_11") (pintype "bidirectional"))
    )
    (net (code "46") (name "/MCU{slash}PC4{slash}Analog_IN14") (class "Default")
      (node (ref "Port C1") (pin "5") (pinfunction "5_5") (pintype "passive"))
      (node (ref "U1") (pin "24") (pinfunction "PC4/I2S1_MCK/SPDIFRX_IN2/FMC_SDNE0/EVENTOUT_24") (pintype "bidirectional"))
    )
    (net (code "47") (name "/MCU{slash}PC5{slash}Analog_IN15") (class "Default")
      (node (ref "Port C1") (pin "6") (pinfunction "6_6") (pintype "passive"))
      (node (ref "U1") (pin "25") (pinfunction "PC5/USART3_RX/SPDIFRX_IN3/FMC_SDCKE0/EVENTOUT_25") (pintype "bidirectional"))
    )
    (net (code "48") (name "/MCU{slash}PC6") (class "Default")
      (node (ref "Port C1") (pin "7") (pinfunction "7_7") (pintype "passive"))
      (node (ref "U1") (pin "37") (pinfunction "PC6/TIM3_CH1/TIM8_CH1/FMPI2C1_SCL/I2S2_MCK/USART6_TX/SDIO_D6/DCMI_D0/EVENTOUT_37") (pintype "bidirectional"))
    )
    (net (code "49") (name "/MCU{slash}PC7") (class "Default")
      (node (ref "Port C1") (pin "16") (pinfunction "16_16") (pintype "passive"))
      (node (ref "U1") (pin "38") (pinfunction "PC7/TIM3_CH2/TIM8_CH2/FMPI2C1_SDA/SPI2_SCK/I2S2_CK/I2S3_MCK/SPDIFRX_IN1/USART6_RX/SDIO_D7/DCMI_D1/EVENTOUT_38") (pintype "bidirectional"))
    )
    (net (code "50") (name "/MCU{slash}PC8") (class "Default")
      (node (ref "Port C1") (pin "15") (pinfunction "15_15") (pintype "passive"))
      (node (ref "U1") (pin "39") (pinfunction "PC8/TRACED0/TIM3_CH3/TIM8_CH3/UART5_RTS/USART6_CK/SDIO_D0/DCMI_D2/EVENTOUT_39") (pintype "bidirectional"))
    )
    (net (code "51") (name "/MCU{slash}PC9") (class "Default")
      (node (ref "Port C1") (pin "14") (pinfunction "14_14") (pintype "passive"))
      (node (ref "U1") (pin "40") (pinfunction "PC9/MCO2/TIM3_CH4/TIM8_CH4/I2C3_SDA/I2S_CKIN/UART5_CTS/QUADSPI_BK1_IO0/SDIO_D1/DCMI_D3/EVENTOUT_40") (pintype "bidirectional"))
    )
    (net (code "52") (name "/MCU{slash}PC10") (class "Default")
      (node (ref "Port C1") (pin "13") (pinfunction "13_13") (pintype "passive"))
      (node (ref "U1") (pin "51") (pinfunction "PC10/SPI3_SCK/I2S3_CK/USART3_TX/UART4_TX/QUADSPI_BK1_IO1/SDIO_D2/DCMI_D8/EVENTOUT_51") (pintype "bidirectional"))
    )
    (net (code "53") (name "/MCU{slash}PC11") (class "Default")
      (node (ref "Port C1") (pin "12") (pinfunction "12_12") (pintype "passive"))
      (node (ref "U1") (pin "52") (pinfunction "PC11/SPI3_MISO/USART3_RX/UART4_RX/QUADSPI_BK2_NCS/SDIO_D3/DCMI_D4/EVENTOUT_52") (pintype "bidirectional"))
    )
    (net (code "54") (name "/MCU{slash}PC12") (class "Default")
      (node (ref "Port C1") (pin "11") (pinfunction "11_11") (pintype "passive"))
      (node (ref "U1") (pin "53") (pinfunction "PC12/I2C2_SDA/SPI3_MOSI/I2S3_SD/USART3_CK/UART5_TX/SDIO_CK/DCMI_D9/EVENTOUT_53") (pintype "bidirectional"))
    )
    (net (code "55") (name "/MCU{slash}PC13") (class "Default")
      (node (ref "Port C1") (pin "10") (pinfunction "10_10") (pintype "passive"))
      (node (ref "U1") (pin "2") (pinfunction "PC13/EVENTOUT_2") (pintype "bidirectional"))
    )
    (net (code "56") (name "/MCU{slash}PD2") (class "Default")
      (node (ref "Port C1") (pin "9") (pinfunction "9_9") (pintype "passive"))
      (node (ref "U1") (pin "54") (pinfunction "PD2/TIM3_ETR/UART5_RX/SDIO_CMD/DCMI_D11/EVENTOUT_54") (pintype "bidirectional"))
    )
    (net (code "57") (name "/NRST") (class "Default")
      (node (ref "BT1") (pin "1") (pintype "passive"))
      (node (ref "BT1") (pin "3") (pintype "passive"))
      (node (ref "R1") (pin "2") (pinfunction "2_2") (pintype "passive"))
      (node (ref "SWD") (pin "8") (pinfunction "8_8") (pintype "passive"))
      (node (ref "U1") (pin "7") (pinfunction "NRST_7") (pintype "bidirectional"))
    )
    (net (code "58") (name "/Operate") (class "Default")
      (node (ref "J1") (pin "1") (pinfunction "1_1") (pintype "bidirectional"))
      (node (ref "R3") (pin "1") (pinfunction "1_1") (pintype "passive"))
    )
    (net (code "59") (name "GND") (class "Default")
      (node (ref "AMS1") (pin "1") (pinfunction "GND_1") (pintype "passive"))
      (node (ref "BT1") (pin "2") (pintype "passive"))
      (node (ref "BT1") (pin "4") (pintype "passive"))
      (node (ref "C1") (pin "2") (pinfunction "2_2") (pintype "passive"))
      (node (ref "C10") (pin "2") (pinfunction "2_2") (pintype "passive"))
      (node (ref "C11") (pin "1") (pinfunction "1_1") (pintype "passive"))
      (node (ref "C12") (pin "2") (pinfunction "2_2") (pintype "passive"))
      (node (ref "C13") (pin "2") (pinfunction "2_2") (pintype "passive"))
      (node (ref "C14") (pin "2") (pinfunction "2_2") (pintype "passive"))
      (node (ref "C15") (pin "2") (pinfunction "2_2") (pintype "passive"))
      (node (ref "C16") (pin "2") (pinfunction "2_2") (pintype "passive"))
      (node (ref "C17") (pin "2") (pinfunction "2_2") (pintype "passive"))
      (node (ref "C18") (pin "2") (pinfunction "2_2") (pintype "passive"))
      (node (ref "C19") (pin "2") (pinfunction "2_2") (pintype "passive"))
      (node (ref "C2") (pin "2") (pinfunction "2_2") (pintype "passive"))
      (node (ref "C20") (pin "2") (pinfunction "2_2") (pintype "passive"))
      (node (ref "C21") (pin "2") (pinfunction "2_2") (pintype "passive"))
      (node (ref "C22") (pin "1") (pinfunction "1_1") (pintype "passive"))
      (node (ref "C3") (pin "2") (pinfunction "2_2") (pintype "passive"))
      (node (ref "C4") (pin "2") (pinfunction "2_2") (pintype "passive"))
      (node (ref "C5") (pin "2") (pinfunction "2_2") (pintype "passive"))
      (node (ref "C6") (pin "2") (pinfunction "2_2") (pintype "passive"))
      (node (ref "C7") (pin "2") (pinfunction "2_2") (pintype "passive"))
      (node (ref "C8") (pin "2") (pinfunction "2_2") (pintype "passive"))
      (node (ref "C9") (pin "2") (pinfunction "2_2") (pintype "passive"))
      (node (ref "CAN 1") (pin "1") (pinfunction "1_1") (pintype "passive"))
      (node (ref "CAN1") (pin "2") (pinfunction "VSS_2") (pintype "power_in"))
      (node (ref "J2") (pin "5") (pinfunction "GND_5") (pintype "power_in"))
      (node (ref "MD1") (pin "1") (pinfunction "GND_1") (pintype "passive"))
      (node (ref "Port A1") (pin "17") (pinfunction "17_17") (pintype "passive"))
      (node (ref "Port B1") (pin "9") (pinfunction "9_9") (pintype "passive"))
      (node (ref "Port C1") (pin "8") (pinfunction "8_8") (pintype "passive"))
      (node (ref "R12") (pin "2") (pinfunction "2_2") (pintype "passive"))
      (node (ref "R13") (pin "1") (pinfunction "1_1") (pintype "passive"))
      (node (ref "R18") (pin "1") (pinfunction "1_1") (pintype "passive"))
      (node (ref "R3") (pin "2") (pinfunction "2_2") (pintype "passive"))
      (node (ref "R4") (pin "1") (pinfunction "1_1") (pintype "passive"))
      (node (ref "SWD") (pin "11") (pinfunction "11_11") (pintype "passive"))
      (node (ref "SWD") (pin "12") (pinfunction "12_12") (pintype "passive"))
      (node (ref "SWD") (pin "13") (pinfunction "13_13") (pintype "passive"))
      (node (ref "SWD") (pin "14") (pinfunction "14_14") (pintype "passive"))
      (node (ref "SWD") (pin "15") (pinfunction "15_15") (pintype "passive"))
      (node (ref "SWD") (pin "16") (pinfunction "16_16") (pintype "passive"))
      (node (ref "SWD") (pin "17") (pinfunction "17_17") (pintype "passive"))
      (node (ref "SWD") (pin "18") (pinfunction "18_18") (pintype "passive"))
      (node (ref "SWD") (pin "19") (pinfunction "19_19") (pintype "passive"))
      (node (ref "Servo/PWM1") (pin "10") (pinfunction "10_10") (pintype "passive"))
      (node (ref "Servo/PWM1") (pin "3") (pinfunction "3_3") (pintype "passive"))
      (node (ref "Servo/PWM1") (pin "6") (pinfunction "6_6") (pintype "passive"))
      (node (ref "Servo/PWM1") (pin "7") (pinfunction "7_7") (pintype "passive"))
      (node (ref "U1") (pin "12") (pinfunction "VSSA/VREF-_12") (pintype "power_in"))
      (node (ref "U1") (pin "18") (pinfunction "VSS_18") (pintype "power_in"))
      (node (ref "U1") (pin "31") (pinfunction "VSS_31") (pintype "power_in"))
      (node (ref "U1") (pin "47") (pinfunction "VSS_47") (pintype "power_in"))
      (node (ref "U1") (pin "63") (pinfunction "VSS_63") (pintype "power_in"))
      (node (ref "U2") (pin "11") (pinfunction "FSYNC_11") (pintype "input"))
      (node (ref "U2") (pin "18") (pinfunction "GND_18") (pintype "power_in"))
      (node (ref "U2") (pin "20") (pinfunction "RESV_20_20") (pintype "power_in"))
      (node (ref "U2") (pin "25") (pinfunction "EXP_25") (pintype "passive"))
    )
    (net (code "60") (name "Net-(C12-Pad1)") (class "Default")
      (node (ref "C12") (pin "1") (pinfunction "1_1") (pintype "passive"))
      (node (ref "R6") (pin "1") (pinfunction "1_1") (pintype "passive"))
    )
    (net (code "61") (name "Net-(C13-Pad1)") (class "Default")
      (node (ref "C13") (pin "1") (pinfunction "1_1") (pintype "passive"))
      (node (ref "R7") (pin "1") (pinfunction "1_1") (pintype "passive"))
    )
    (net (code "62") (name "Net-(CAN1-RS)") (class "Default")
      (node (ref "CAN1") (pin "8") (pinfunction "RS_8") (pintype "input"))
      (node (ref "R4") (pin "2") (pinfunction "2_2") (pintype "passive"))
    )
    (net (code "63") (name "Net-(J2-D+)") (class "Default")
      (node (ref "J2") (pin "3") (pinfunction "D+_3") (pintype "bidirectional"))
      (node (ref "R10") (pin "1") (pinfunction "1_1") (pintype "passive"))
    )
    (net (code "64") (name "Net-(J2-D-)") (class "Default")
      (node (ref "J2") (pin "2") (pinfunction "D-_2") (pintype "bidirectional"))
      (node (ref "R9") (pin "1") (pinfunction "1_1") (pintype "passive"))
    )
    (net (code "65") (name "Net-(L2-K)") (class "Default")
      (node (ref "L2") (pin "2") (pinfunction "K_2") (pintype "passive"))
      (node (ref "R12") (pin "1") (pinfunction "1_1") (pintype "passive"))
    )
    (net (code "66") (name "Net-(L3-K)") (class "Default")
      (node (ref "L3") (pin "2") (pinfunction "K_2") (pintype "passive"))
      (node (ref "R13") (pin "2") (pinfunction "2_2") (pintype "passive"))
    )
    (net (code "67") (name "Net-(U2-REGOUT)") (class "Default")
      (node (ref "C11") (pin "2") (pinfunction "2_2") (pintype "passive"))
      (node (ref "U2") (pin "10") (pinfunction "REGOUT_10") (pintype "output"))
    )
    (net (code "68") (name "VCC") (class "Default")
      (node (ref "C17") (pin "1") (pinfunction "1_1") (pintype "passive"))
      (node (ref "J2") (pin "1") (pinfunction "VCC_1") (pintype "power_in"))
      (node (ref "L1") (pin "2") (pinfunction "2_2") (pintype "passive"))
    )
    (net (code "69") (name "unconnected-(CAN1-VREF-Pad5)") (class "Default")
      (node (ref "CAN1") (pin "5") (pinfunction "VREF_5") (pintype "output+no_connect"))
    )
    (net (code "70") (name "unconnected-(J2-ID-Pad4)") (class "Default")
      (node (ref "J2") (pin "4") (pinfunction "ID_4") (pintype "bidirectional+no_connect"))
    )
    (net (code "71") (name "unconnected-(J2-SHIELD-Pad6)") (class "Default")
      (node (ref "J2") (pin "6") (pinfunction "SHIELD_6") (pintype "passive+no_connect"))
    )
    (net (code "72") (name "unconnected-(J2-SHIELD-Pad7)") (class "Default")
      (node (ref "J2") (pin "7") (pinfunction "SHIELD_7") (pintype "passive+no_connect"))
    )
    (net (code "73") (name "unconnected-(J2-SHIELD-Pad8)") (class "Default")
      (node (ref "J2") (pin "8") (pinfunction "SHIELD_8") (pintype "passive+no_connect"))
    )
    (net (code "74") (name "unconnected-(J2-SHIELD-Pad9)") (class "Default")
      (node (ref "J2") (pin "9") (pinfunction "SHIELD_9") (pintype "passive+no_connect"))
    )
    (net (code "75") (name "unconnected-(J2-SHIELD-Pad10)") (class "Default")
      (node (ref "J2") (pin "10") (pinfunction "SHIELD_10") (pintype "passive+no_connect"))
    )
    (net (code "76") (name "unconnected-(J2-SHIELD-Pad11)") (class "Default")
      (node (ref "J2") (pin "11") (pinfunction "SHIELD_11") (pintype "passive+no_connect"))
    )
    (net (code "77") (name "unconnected-(J2-SHIELD-PadS1)") (class "Default")
      (node (ref "J2") (pin "S1") (pinfunction "SHIELD_S1") (pintype "passive+no_connect"))
    )
    (net (code "78") (name "unconnected-(J2-SHIELD-PadS2)") (class "Default")
      (node (ref "J2") (pin "S2") (pinfunction "SHIELD_S2") (pintype "passive+no_connect"))
    )
    (net (code "79") (name "unconnected-(SWD-Pad6)") (class "Default")
      (node (ref "SWD") (pin "6") (pinfunction "6_6") (pintype "passive+no_connect"))
    )
    (net (code "80") (name "unconnected-(SWD-Pad9)") (class "Default")
      (node (ref "SWD") (pin "9") (pinfunction "9_9") (pintype "passive+no_connect"))
    )
    (net (code "81") (name "unconnected-(SWD-Pad10)") (class "Default")
      (node (ref "SWD") (pin "10") (pinfunction "10_10") (pintype "passive+no_connect"))
    )
    (net (code "82") (name "unconnected-(U2-AUX_CL-Pad7)") (class "Default")
      (node (ref "U2") (pin "7") (pinfunction "AUX_CL_7") (pintype "input+no_connect"))
    )
    (net (code "83") (name "unconnected-(U2-AUX_DA-Pad21)") (class "Default")
      (node (ref "U2") (pin "21") (pinfunction "AUX_DA_21") (pintype "input+no_connect"))
    )
    (net (code "84") (name "unconnected-(U2-NC-Pad2)") (class "Default")
      (node (ref "U2") (pin "2") (pinfunction "NC_2") (pintype "passive+no_connect"))
    )
    (net (code "85") (name "unconnected-(U2-NC-Pad3)") (class "Default")
      (node (ref "U2") (pin "3") (pinfunction "NC_3") (pintype "passive+no_connect"))
    )
    (net (code "86") (name "unconnected-(U2-NC-Pad4)") (class "Default")
      (node (ref "U2") (pin "4") (pinfunction "NC_4") (pintype "passive+no_connect"))
    )
    (net (code "87") (name "unconnected-(U2-NC-Pad5)") (class "Default")
      (node (ref "U2") (pin "5") (pinfunction "NC_5") (pintype "passive+no_connect"))
    )
    (net (code "88") (name "unconnected-(U2-NC-Pad6)") (class "Default")
      (node (ref "U2") (pin "6") (pinfunction "NC_6") (pintype "passive+no_connect"))
    )
    (net (code "89") (name "unconnected-(U2-NC-Pad14)") (class "Default")
      (node (ref "U2") (pin "14") (pinfunction "NC_14") (pintype "passive+no_connect"))
    )
    (net (code "90") (name "unconnected-(U2-NC-Pad15)") (class "Default")
      (node (ref "U2") (pin "15") (pinfunction "NC_15") (pintype "passive+no_connect"))
    )
    (net (code "91") (name "unconnected-(U2-NC-Pad16)") (class "Default")
      (node (ref "U2") (pin "16") (pinfunction "NC_16") (pintype "passive+no_connect"))
    )
    (net (code "92") (name "unconnected-(U2-NC-Pad17)") (class "Default")
      (node (ref "U2") (pin "17") (pinfunction "NC_17") (pintype "passive+no_connect"))
    )
    (net (code "93") (name "unconnected-(U2-RESV_19-Pad19)") (class "Default")
      (node (ref "U2") (pin "19") (pinfunction "RESV_19_19") (pintype "passive"))
    )
  )
)
